# V831.net
KiCad netlist of a schematic drawn in Altium Designer
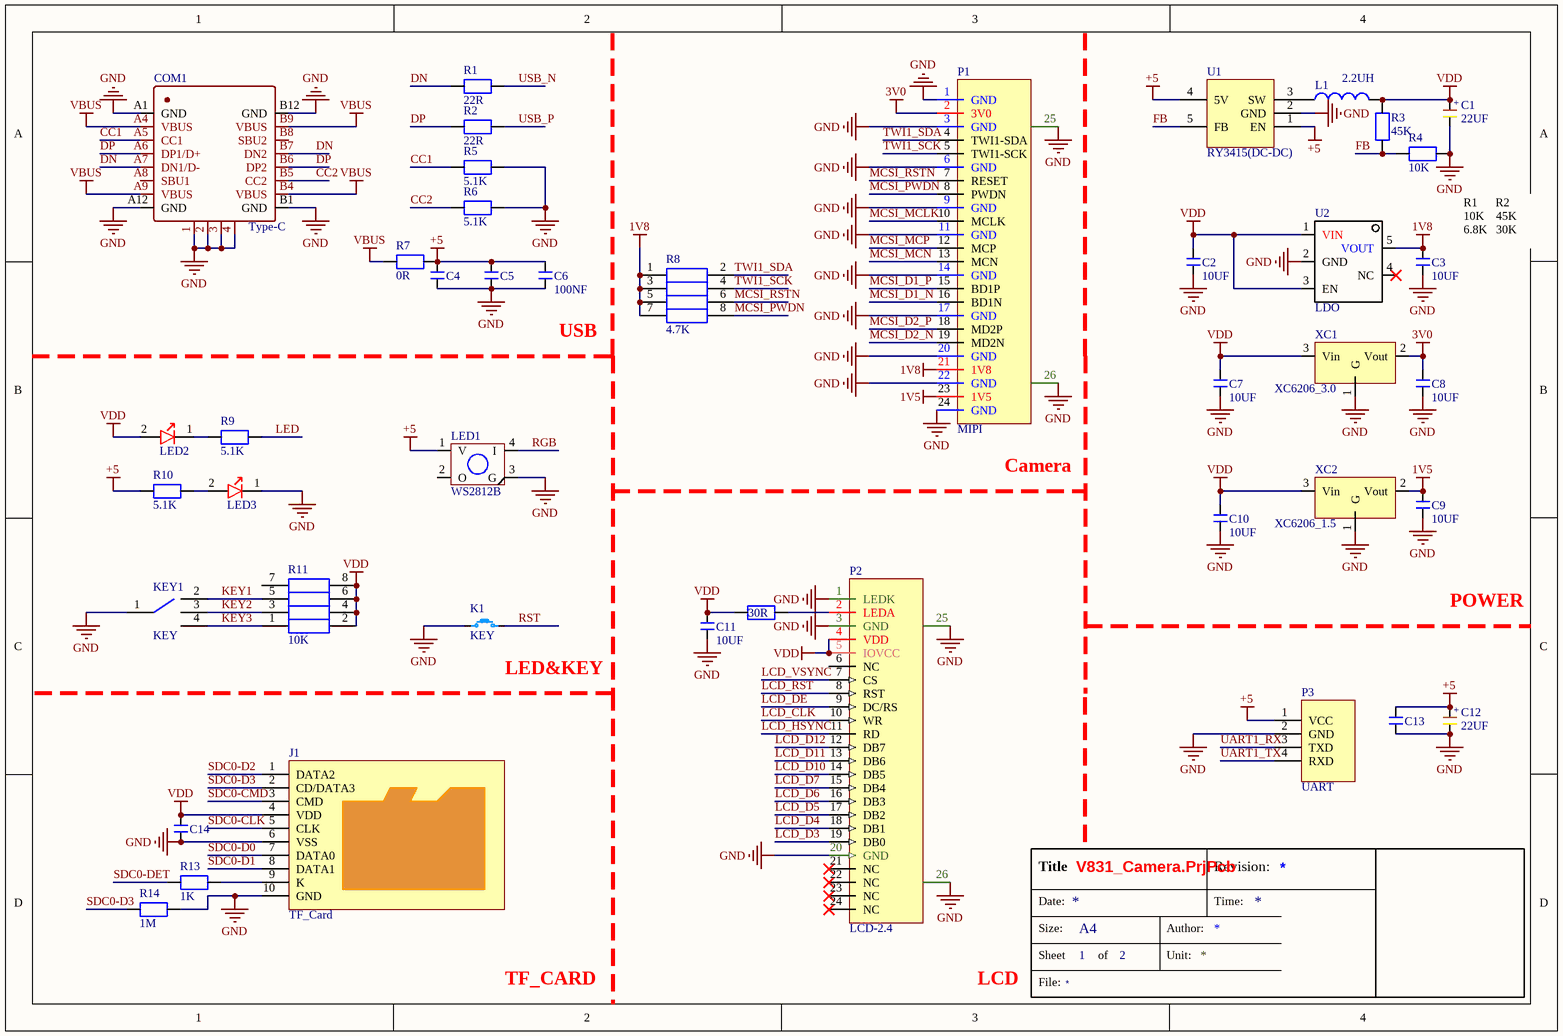
[diagram p0: V831.SchDoc]

(export (version "E")
  (design (tool "Eeschema 10.0.6"))
  (components
    (comp (ref "C1")
      (value "22UF")
      (footprint "CAP_3216_A")
      (description "CAP  6~12V  钽电容")
      (libsource (lib "User") (part "CAP_TA"))
    )
    (comp (ref "C2")
      (value "10UF")
      (footprint "CAP_1206")
      (description "CAP  12~50V")
      (libsource (lib "User") (part "CAP"))
    )
    (comp (ref "C3")
      (value "10UF")
      (footprint "CAP_0603")
      (description "CAP  12~50V")
      (libsource (lib "User") (part "CAP"))
    )
    (comp (ref "C4")
      (value "100NF")
      (footprint "CAP_0603")
      (description "CAP  12~50V")
      (libsource (lib "User") (part "CAP"))
    )
    (comp (ref "C5")
      (value "100NF")
      (footprint "CAP_0603")
      (description "CAP  12~50V")
      (libsource (lib "User") (part "CAP"))
    )
    (comp (ref "C6")
      (value "100NF")
      (footprint "CAP_0603")
      (description "CAP  12~50V")
      (libsource (lib "User") (part "CAP"))
    )
    (comp (ref "C7")
      (value "10UF")
      (footprint "CAP_0603")
      (description "CAP  12~50V")
      (libsource (lib "User") (part "CAP"))
    )
    (comp (ref "C8")
      (value "10UF")
      (footprint "CAP_0603")
      (description "CAP  12~50V")
      (libsource (lib "User") (part "CAP"))
    )
    (comp (ref "C9")
      (value "10UF")
      (footprint "CAP_0603")
      (description "CAP  12~50V")
      (libsource (lib "User") (part "CAP"))
    )
    (comp (ref "C10")
      (value "10UF")
      (footprint "CAP_0603")
      (description "CAP  12~50V")
      (libsource (lib "User") (part "CAP"))
    )
    (comp (ref "C11")
      (value "10UF")
      (footprint "CAP_0603")
      (description "CAP  12~50V")
      (libsource (lib "User") (part "CAP"))
    )
    (comp (ref "C12")
      (value "22UF")
      (footprint "CAP_3216_A")
      (description "CAP  6~12V  钽电容")
      (libsource (lib "User") (part "CAP_TA"))
    )
    (comp (ref "C13")
      (value "100NF")
      (footprint "CAP_0603")
      (description "CAP  12~50V")
      (libsource (lib "User") (part "CAP"))
    )
    (comp (ref "C14")
      (value "100NF")
      (footprint "CAP_0603")
      (description "CAP  12~50V")
      (libsource (lib "User") (part "CAP"))
    )
    (comp (ref "COM1")
      (value "Type-C")
      (footprint "USB-Type-C_16A")
      (description "USB")
      (libsource (lib "User") (part "USB-type_c"))
    )
    (comp (ref "J1")
      (value "TF_Card")
      (footprint "TF_Card")
      (description "TF卡座")
      (libsource (lib "User") (part "TF_Card"))
    )
    (comp (ref "K1")
      (value "KEY")
      (footprint "KEY_SMD-4P")
      (description "Key")
      (libsource (lib "User") (part "KEY"))
    )
    (comp (ref "KEY1")
      (value "KEY")
      (footprint "KEY-K1-1502SA-LY-K3")
      (libsource (lib "User") (part "LY-K3"))
    )
    (comp (ref "L1")
      (value "2.2UH")
      (footprint "INDUCTANCE_4*4")
      (description "Inductor")
      (fields (field (name "PUBLISHER") "Altium Limited"))
      (libsource (lib "User") (part "Inductor"))
    )
    (comp (ref "LED1")
      (value "WS2812B")
      (footprint "WS2812B")
      (description "LED")
      (libsource (lib "User") (part "WS2812B"))
    )
    (comp (ref "LED2")
      (value "LED_R/G/B/Y")
      (footprint "LED_0603_B")
      (description "LED")
      (libsource (lib "User") (part "LED_SMT"))
    )
    (comp (ref "LED3")
      (value "LED_R/G/B/Y")
      (footprint "LED_0603_R")
      (description "LED")
      (libsource (lib "User") (part "LED_SMT"))
    )
    (comp (ref "P1")
      (value "MIPI")
      (footprint "FPC-24Pin")
      (description "OV2465&VS3205")
      (libsource (lib "User") (part "MIPI"))
    )
    (comp (ref "P2")
      (value "LCD-2.4")
      (footprint "FPC-24PIN-FB")
      (description "Show 2.4-2.8寸")
      (libsource (lib "User") (part "LCD-ST7789-Pin24"))
    )
    (comp (ref "P3")
      (value "UART")
      (footprint "XH2.54-WS-4P")
      (description "Header")
      (libsource (lib "User") (part "UART"))
    )
    (comp (ref "R1")
      (value "22R")
      (footprint "RESC_0603_2")
      (description "RES 贴片")
      (libsource (lib "User") (part "RES"))
    )
    (comp (ref "R2")
      (value "22R")
      (footprint "RESC_0603_2")
      (description "RES 贴片")
      (libsource (lib "User") (part "RES"))
    )
    (comp (ref "R3")
      (value "45K")
      (footprint "RESC_0603_2")
      (description "RES 贴片")
      (libsource (lib "User") (part "RES"))
    )
    (comp (ref "R4")
      (value "10K")
      (footprint "RESC_0603_2")
      (description "RES 贴片")
      (libsource (lib "User") (part "RES"))
    )
    (comp (ref "R5")
      (value "5.1K")
      (footprint "RESC_0603_2")
      (description "RES 贴片")
      (libsource (lib "User") (part "RES"))
    )
    (comp (ref "R6")
      (value "5.1K")
      (footprint "RESC_0603_2")
      (description "RES 贴片")
      (libsource (lib "User") (part "RES"))
    )
    (comp (ref "R7")
      (value "0R")
      (footprint "RESC_0603_2")
      (description "RES 贴片")
      (libsource (lib "User") (part "RES"))
    )
    (comp (ref "R8")
      (value "4.7K")
      (footprint "RESC_0603_4")
      (description "RES")
      (libsource (lib "User") (part "RES_P4"))
    )
    (comp (ref "R9")
      (value "5.1K")
      (footprint "RESC_0603_2")
      (description "RES 贴片")
      (libsource (lib "User") (part "RES"))
    )
    (comp (ref "R10")
      (value "5.1K")
      (footprint "RESC_0603_2")
      (description "RES 贴片")
      (libsource (lib "User") (part "RES"))
    )
    (comp (ref "R11")
      (value "10K")
      (footprint "RESC_0603_4")
      (description "RES")
      (libsource (lib "User") (part "RES_P4"))
    )
    (comp (ref "R12")
      (value "30R")
      (footprint "RESC_0603_2")
      (description "RES 贴片")
      (libsource (lib "User") (part "RES"))
    )
    (comp (ref "R13")
      (value "1K")
      (footprint "RESC_0603_2")
      (description "RES 贴片")
      (libsource (lib "User") (part "RES"))
    )
    (comp (ref "R14")
      (value "1M")
      (footprint "RESC_0603_2")
      (description "RES 贴片")
      (libsource (lib "User") (part "RES"))
    )
    (comp (ref "U1") (value "RY3415(DC-DC)") (footprint "SOT23_5") (libsource (lib "User") (part "RY3415")))
    (comp (ref "U2")
      (value "LDO")
      (footprint "SOT23_5")
      (description "LDO  3.3V  500ma")
      (libsource (lib "User") (part "LDO_SOT23-5"))
    )
    (comp (ref "XC1")
      (value "XC6206_3.0")
      (footprint "SOT23_3")
      (description "DC-DC")
      (libsource (lib "User") (part "XC6206"))
    )
    (comp (ref "XC2")
      (value "XC6206_1.5")
      (footprint "SOT23_3")
      (description "DC-DC")
      (libsource (lib "User") (part "XC6206"))
    )
  )
  (nets
    (net (code "1") (name "+5") (class "Default")
      (node (ref "C12") (pin "1") (pinfunction "0_1") (pintype "passive"))
      (node (ref "C13") (pin "2") (pinfunction "0_2") (pintype "passive"))
      (node (ref "C4") (pin "2") (pinfunction "0_2") (pintype "passive"))
      (node (ref "C5") (pin "2") (pinfunction "0_2") (pintype "passive"))
      (node (ref "C6") (pin "2") (pinfunction "0_2") (pintype "passive"))
      (node (ref "LED1") (pin "1") (pinfunction "V_1") (pintype "passive"))
      (node (ref "P3") (pin "1") (pinfunction "VCC_1") (pintype "passive"))
      (node (ref "R10") (pin "1") (pinfunction "1_1") (pintype "passive"))
      (node (ref "R7") (pin "2") (pinfunction "2_2") (pintype "passive"))
      (node (ref "U1") (pin "1") (pinfunction "EN_1") (pintype "passive"))
      (node (ref "U1") (pin "4") (pinfunction "5V_4") (pintype "passive"))
    )
    (net (code "2") (name "/CC1") (class "Default")
      (node (ref "COM1") (pin "A5") (pinfunction "CC1_A5") (pintype "passive"))
      (node (ref "R5") (pin "1") (pinfunction "1_1") (pintype "passive"))
    )
    (net (code "3") (name "/CC2") (class "Default")
      (node (ref "COM1") (pin "B5") (pinfunction "CC2_B5") (pintype "passive"))
      (node (ref "R6") (pin "1") (pinfunction "1_1") (pintype "passive"))
    )
    (net (code "4") (name "/DN") (class "Default")
      (node (ref "COM1") (pin "A7") (pinfunction "DN1/D-_A7") (pintype "passive"))
      (node (ref "COM1") (pin "B7") (pinfunction "DN2_B7") (pintype "passive"))
      (node (ref "R1") (pin "1") (pinfunction "1_1") (pintype "passive"))
    )
    (net (code "5") (name "/DP") (class "Default")
      (node (ref "COM1") (pin "A6") (pinfunction "DP1/D+_A6") (pintype "passive"))
      (node (ref "COM1") (pin "B6") (pinfunction "DP2_B6") (pintype "passive"))
      (node (ref "R2") (pin "1") (pinfunction "1_1") (pintype "passive"))
    )
    (net (code "6") (name "/FB") (class "Default")
      (node (ref "R3") (pin "2") (pinfunction "2_2") (pintype "passive"))
      (node (ref "R4") (pin "1") (pinfunction "1_1") (pintype "passive"))
      (node (ref "U1") (pin "5") (pinfunction "FB_5") (pintype "passive"))
    )
    (net (code "7") (name "/KEY1") (class "Default")
      (node (ref "KEY1") (pin "2") (pinfunction "2_2") (pintype "passive"))
      (node (ref "R11") (pin "5") (pinfunction "5_5") (pintype "passive"))
    )
    (net (code "8") (name "/KEY2") (class "Default")
      (node (ref "KEY1") (pin "3") (pinfunction "3_3") (pintype "passive"))
      (node (ref "R11") (pin "3") (pinfunction "3_3") (pintype "passive"))
    )
    (net (code "9") (name "/KEY3") (class "Default")
      (node (ref "KEY1") (pin "4") (pinfunction "4_4") (pintype "passive"))
      (node (ref "R11") (pin "1") (pinfunction "1_1") (pintype "passive"))
    )
    (net (code "10") (name "/LCD_CLK") (class "Default")
      (node (ref "P2") (pin "10") (pinfunction "WR_10") (pintype "input"))
    )
    (net (code "11") (name "/LCD_D3") (class "Default")
      (node (ref "P2") (pin "19") (pinfunction "DB0_19") (pintype "input"))
    )
    (net (code "12") (name "/LCD_D4") (class "Default")
      (node (ref "P2") (pin "18") (pinfunction "DB1_18") (pintype "input"))
    )
    (net (code "13") (name "/LCD_D5") (class "Default")
      (node (ref "P2") (pin "17") (pinfunction "DB2_17") (pintype "input"))
    )
    (net (code "14") (name "/LCD_D6") (class "Default")
      (node (ref "P2") (pin "16") (pinfunction "DB3_16") (pintype "input"))
    )
    (net (code "15") (name "/LCD_D7") (class "Default")
      (node (ref "P2") (pin "15") (pinfunction "DB4_15") (pintype "input"))
    )
    (net (code "16") (name "/LCD_D10") (class "Default")
      (node (ref "P2") (pin "14") (pinfunction "DB5_14") (pintype "input"))
    )
    (net (code "17") (name "/LCD_D11") (class "Default")
      (node (ref "P2") (pin "13") (pinfunction "DB6_13") (pintype "input"))
    )
    (net (code "18") (name "/LCD_D12") (class "Default")
      (node (ref "P2") (pin "12") (pinfunction "DB7_12") (pintype "input"))
    )
    (net (code "19") (name "/LCD_DE") (class "Default")
      (node (ref "P2") (pin "9") (pinfunction "DC/RS_9") (pintype "input"))
    )
    (net (code "20") (name "/LCD_HSYNC") (class "Default")
      (node (ref "P2") (pin "11") (pinfunction "RD_11") (pintype "passive"))
    )
    (net (code "21") (name "/LCD_RST") (class "Default")
      (node (ref "P2") (pin "8") (pinfunction "RST_8") (pintype "input"))
    )
    (net (code "22") (name "/LCD_VSYNC") (class "Default")
      (node (ref "P2") (pin "7") (pinfunction "CS_7") (pintype "input"))
    )
    (net (code "23") (name "/LED") (class "Default")
      (node (ref "R9") (pin "2") (pinfunction "2_2") (pintype "passive"))
    )
    (net (code "24") (name "/MCSI_D1_N") (class "Default")
      (node (ref "P1") (pin "16") (pinfunction "BD1N_16") (pintype "passive"))
    )
    (net (code "25") (name "/MCSI_D1_P") (class "Default")
      (node (ref "P1") (pin "15") (pinfunction "BD1P_15") (pintype "passive"))
    )
    (net (code "26") (name "/MCSI_D2_N") (class "Default")
      (node (ref "P1") (pin "19") (pinfunction "MD2N_19") (pintype "passive"))
    )
    (net (code "27") (name "/MCSI_D2_P") (class "Default")
      (node (ref "P1") (pin "18") (pinfunction "MD2P_18") (pintype "passive"))
    )
    (net (code "28") (name "/MCSI_MCLK") (class "Default")
      (node (ref "P1") (pin "10") (pinfunction "MCLK_10") (pintype "passive"))
    )
    (net (code "29") (name "/MCSI_MCN") (class "Default")
      (node (ref "P1") (pin "13") (pinfunction "MCN_13") (pintype "passive"))
    )
    (net (code "30") (name "/MCSI_MCP") (class "Default")
      (node (ref "P1") (pin "12") (pinfunction "MCP_12") (pintype "passive"))
    )
    (net (code "31") (name "/MCSI_PWDN") (class "Default")
      (node (ref "P1") (pin "8") (pinfunction "PWDN_8") (pintype "passive"))
      (node (ref "R8") (pin "8") (pinfunction "8_8") (pintype "passive"))
    )
    (net (code "32") (name "/MCSI_RSTN") (class "Default")
      (node (ref "P1") (pin "7") (pinfunction "RESET_7") (pintype "passive"))
      (node (ref "R8") (pin "6") (pinfunction "6_6") (pintype "passive"))
    )
    (net (code "33") (name "/RGB") (class "Default")
      (node (ref "LED1") (pin "4") (pinfunction "I_4") (pintype "passive"))
    )
    (net (code "34") (name "/RST") (class "Default") (node (ref "K1") (pin "2") (pintype "passive")))
    (net (code "35") (name "/SDC0-CLK") (class "Default")
      (node (ref "J1") (pin "5") (pinfunction "CLK_5") (pintype "passive"))
    )
    (net (code "36") (name "/SDC0-CMD") (class "Default")
      (node (ref "J1") (pin "3") (pinfunction "CMD_3") (pintype "passive"))
    )
    (net (code "37") (name "/SDC0-D0") (class "Default")
      (node (ref "J1") (pin "7") (pinfunction "DATA0_7") (pintype "passive"))
    )
    (net (code "38") (name "/SDC0-D1") (class "Default")
      (node (ref "J1") (pin "8") (pinfunction "DATA1_8") (pintype "passive"))
    )
    (net (code "39") (name "/SDC0-D2") (class "Default")
      (node (ref "J1") (pin "1") (pinfunction "DATA2_1") (pintype "passive"))
    )
    (net (code "40") (name "/SDC0-D3") (class "Default")
      (node (ref "J1") (pin "2") (pinfunction "CD/DATA3_2") (pintype "passive"))
      (node (ref "R14") (pin "1") (pinfunction "1_1") (pintype "passive"))
    )
    (net (code "41") (name "/SDC0-DET") (class "Default")
      (node (ref "R13") (pin "1") (pinfunction "1_1") (pintype "passive"))
    )
    (net (code "42") (name "/TWI1_SCK") (class "Default")
      (node (ref "P1") (pin "5") (pinfunction "TWI1-SCK_5") (pintype "passive"))
      (node (ref "R8") (pin "4") (pinfunction "4_4") (pintype "passive"))
    )
    (net (code "43") (name "/TWI1_SDA") (class "Default")
      (node (ref "P1") (pin "4") (pinfunction "TWI1-SDA_4") (pintype "passive"))
      (node (ref "R8") (pin "2") (pinfunction "2_2") (pintype "passive"))
    )
    (net (code "44") (name "/UART1_RX") (class "Default")
      (node (ref "P3") (pin "3") (pinfunction "TXD_3") (pintype "passive"))
    )
    (net (code "45") (name "/UART1_TX") (class "Default")
      (node (ref "P3") (pin "4") (pinfunction "RXD_4") (pintype "passive"))
    )
    (net (code "46") (name "/USB_N") (class "Default")
      (node (ref "R1") (pin "2") (pinfunction "2_2") (pintype "passive"))
    )
    (net (code "47") (name "/USB_P") (class "Default")
      (node (ref "R2") (pin "2") (pinfunction "2_2") (pintype "passive"))
    )
    (net (code "48") (name "1V5") (class "Default")
      (node (ref "C9") (pin "2") (pinfunction "0_2") (pintype "passive"))
      (node (ref "P1") (pin "23") (pinfunction "1V5_23") (pintype "passive"))
      (node (ref "XC2") (pin "2") (pinfunction "Vout_2") (pintype "passive"))
    )
    (net (code "49") (name "1V8") (class "Default")
      (node (ref "C3") (pin "2") (pinfunction "0_2") (pintype "passive"))
      (node (ref "P1") (pin "21") (pinfunction "1V8_21") (pintype "passive"))
      (node (ref "R8") (pin "1") (pinfunction "1_1") (pintype "passive"))
      (node (ref "R8") (pin "3") (pinfunction "3_3") (pintype "passive"))
      (node (ref "R8") (pin "5") (pinfunction "5_5") (pintype "passive"))
      (node (ref "R8") (pin "7") (pinfunction "7_7") (pintype "passive"))
      (node (ref "U2") (pin "5") (pinfunction "VOUT_5") (pintype "passive"))
    )
    (net (code "50") (name "3V0") (class "Default")
      (node (ref "C8") (pin "2") (pinfunction "0_2") (pintype "passive"))
      (node (ref "P1") (pin "2") (pinfunction "3V0_2") (pintype "passive"))
      (node (ref "XC1") (pin "2") (pinfunction "Vout_2") (pintype "passive"))
    )
    (net (code "51") (name "GND") (class "Default")
      (node (ref "C1") (pin "2") (pinfunction "0_2") (pintype "passive"))
      (node (ref "C10") (pin "1") (pinfunction "0_1") (pintype "passive"))
      (node (ref "C11") (pin "1") (pinfunction "0_1") (pintype "passive"))
      (node (ref "C12") (pin "2") (pinfunction "0_2") (pintype "passive"))
      (node (ref "C13") (pin "1") (pinfunction "0_1") (pintype "passive"))
      (node (ref "C14") (pin "1") (pinfunction "0_1") (pintype "passive"))
      (node (ref "C2") (pin "1") (pinfunction "0_1") (pintype "passive"))
      (node (ref "C3") (pin "1") (pinfunction "0_1") (pintype "passive"))
      (node (ref "C4") (pin "1") (pinfunction "0_1") (pintype "passive"))
      (node (ref "C5") (pin "1") (pinfunction "0_1") (pintype "passive"))
      (node (ref "C6") (pin "1") (pinfunction "0_1") (pintype "passive"))
      (node (ref "C7") (pin "1") (pinfunction "0_1") (pintype "passive"))
      (node (ref "C8") (pin "1") (pinfunction "0_1") (pintype "passive"))
      (node (ref "C9") (pin "1") (pinfunction "0_1") (pintype "passive"))
      (node (ref "COM1") (pin "1") (pinfunction "1_1") (pintype "passive"))
      (node (ref "COM1") (pin "2") (pinfunction "2_2") (pintype "passive"))
      (node (ref "COM1") (pin "3") (pinfunction "3_3") (pintype "passive"))
      (node (ref "COM1") (pin "4") (pinfunction "4_4") (pintype "passive"))
      (node (ref "COM1") (pin "A1") (pinfunction "GND_A1") (pintype "passive"))
      (node (ref "COM1") (pin "A12") (pinfunction "GND_A12") (pintype "passive"))
      (node (ref "COM1") (pin "B1") (pinfunction "GND_B1") (pintype "passive"))
      (node (ref "COM1") (pin "B12") (pinfunction "GND_B12") (pintype "passive"))
      (node (ref "J1") (pin "10") (pinfunction "GND_10") (pintype "passive"))
      (node (ref "J1") (pin "6") (pinfunction "VSS_6") (pintype "passive"))
      (node (ref "K1") (pin "1") (pintype "passive"))
      (node (ref "KEY1") (pin "1") (pinfunction "1_1") (pintype "passive"))
      (node (ref "LED1") (pin "3") (pinfunction "G_3") (pintype "passive"))
      (node (ref "LED3") (pin "1") (pinfunction "-_1") (pintype "passive"))
      (node (ref "P1") (pin "1") (pinfunction "GND_1") (pintype "passive"))
      (node (ref "P1") (pin "11") (pinfunction "GND_11") (pintype "passive"))
      (node (ref "P1") (pin "14") (pinfunction "GND_14") (pintype "passive"))
      (node (ref "P1") (pin "17") (pinfunction "GND_17") (pintype "passive"))
      (node (ref "P1") (pin "20") (pinfunction "GND_20") (pintype "passive"))
      (node (ref "P1") (pin "22") (pinfunction "GND_22") (pintype "passive"))
      (node (ref "P1") (pin "24") (pinfunction "GND_24") (pintype "passive"))
      (node (ref "P1") (pin "25") (pinfunction "GND_25") (pintype "passive"))
      (node (ref "P1") (pin "26") (pinfunction "GND_26") (pintype "passive"))
      (node (ref "P1") (pin "3") (pinfunction "GND_3") (pintype "passive"))
      (node (ref "P1") (pin "6") (pinfunction "GND_6") (pintype "passive"))
      (node (ref "P1") (pin "9") (pinfunction "GND_9") (pintype "passive"))
      (node (ref "P2") (pin "1") (pinfunction "LEDK_1") (pintype "passive"))
      (node (ref "P2") (pin "20") (pinfunction "GND_20") (pintype "input"))
      (node (ref "P2") (pin "25") (pinfunction "GND_25") (pintype "passive"))
      (node (ref "P2") (pin "26") (pinfunction "GND_26") (pintype "passive"))
      (node (ref "P2") (pin "3") (pinfunction "GND_3") (pintype "passive"))
      (node (ref "P3") (pin "2") (pinfunction "GND_2") (pintype "passive"))
      (node (ref "R14") (pin "2") (pinfunction "2_2") (pintype "passive"))
      (node (ref "R4") (pin "2") (pinfunction "2_2") (pintype "passive"))
      (node (ref "R5") (pin "2") (pinfunction "2_2") (pintype "passive"))
      (node (ref "R6") (pin "2") (pinfunction "2_2") (pintype "passive"))
      (node (ref "U1") (pin "2") (pinfunction "GND_2") (pintype "passive"))
      (node (ref "U2") (pin "2") (pinfunction "GND_2") (pintype "passive"))
      (node (ref "XC1") (pin "1") (pinfunction "G_1") (pintype "passive"))
      (node (ref "XC2") (pin "1") (pinfunction "G_1") (pintype "passive"))
    )
    (net (code "52") (name "Net-(J1-K)") (class "Default")
      (node (ref "J1") (pin "9") (pinfunction "K_9") (pintype "passive"))
      (node (ref "R13") (pin "2") (pinfunction "2_2") (pintype "passive"))
    )
    (net (code "53") (name "Net-(LED2--)") (class "Default")
      (node (ref "LED2") (pin "1") (pinfunction "-_1") (pintype "passive"))
      (node (ref "R9") (pin "1") (pinfunction "1_1") (pintype "passive"))
    )
    (net (code "54") (name "Net-(LED3-+)") (class "Default")
      (node (ref "LED3") (pin "2") (pinfunction "+_2") (pintype "passive"))
      (node (ref "R10") (pin "2") (pinfunction "2_2") (pintype "passive"))
    )
    (net (code "55") (name "Net-(P2-LEDA)") (class "Default")
      (node (ref "P2") (pin "2") (pinfunction "LEDA_2") (pintype "power_in"))
      (node (ref "R12") (pin "1") (pinfunction "1_1") (pintype "passive"))
    )
    (net (code "56") (name "Net-(U1-SW)") (class "Default")
      (node (ref "L1") (pin "1") (pinfunction "1_1") (pintype "passive"))
      (node (ref "U1") (pin "3") (pinfunction "SW_3") (pintype "passive"))
    )
    (net (code "57") (name "VBUS") (class "Default")
      (node (ref "COM1") (pin "A4") (pinfunction "VBUS_A4") (pintype "passive"))
      (node (ref "COM1") (pin "A9") (pinfunction "VBUS_A9") (pintype "passive"))
      (node (ref "COM1") (pin "B4") (pinfunction "VBUS_B4") (pintype "passive"))
      (node (ref "COM1") (pin "B9") (pinfunction "VBUS_B9") (pintype "passive"))
      (node (ref "R7") (pin "1") (pinfunction "1_1") (pintype "passive"))
    )
    (net (code "58") (name "VDD") (class "Default")
      (node (ref "C1") (pin "1") (pinfunction "0_1") (pintype "passive"))
      (node (ref "C10") (pin "2") (pinfunction "0_2") (pintype "passive"))
      (node (ref "C11") (pin "2") (pinfunction "0_2") (pintype "passive"))
      (node (ref "C14") (pin "2") (pinfunction "0_2") (pintype "passive"))
      (node (ref "C2") (pin "2") (pinfunction "0_2") (pintype "passive"))
      (node (ref "C7") (pin "2") (pinfunction "0_2") (pintype "passive"))
      (node (ref "J1") (pin "4") (pinfunction "VDD_4") (pintype "passive"))
      (node (ref "L1") (pin "2") (pinfunction "2_2") (pintype "passive"))
      (node (ref "LED2") (pin "2") (pinfunction "+_2") (pintype "passive"))
      (node (ref "P2") (pin "4") (pinfunction "VDD_4") (pintype "passive"))
      (node (ref "P2") (pin "5") (pinfunction "IOVCC_5") (pintype "passive"))
      (node (ref "R11") (pin "2") (pinfunction "2_2") (pintype "passive"))
      (node (ref "R11") (pin "4") (pinfunction "4_4") (pintype "passive"))
      (node (ref "R11") (pin "6") (pinfunction "6_6") (pintype "passive"))
      (node (ref "R11") (pin "8") (pinfunction "8_8") (pintype "passive"))
      (node (ref "R12") (pin "2") (pinfunction "2_2") (pintype "passive"))
      (node (ref "R3") (pin "1") (pinfunction "1_1") (pintype "passive"))
      (node (ref "U2") (pin "1") (pinfunction "VIN_1") (pintype "passive"))
      (node (ref "U2") (pin "3") (pinfunction "EN_3") (pintype "passive"))
      (node (ref "XC1") (pin "3") (pinfunction "Vin_3") (pintype "passive"))
      (node (ref "XC2") (pin "3") (pinfunction "Vin_3") (pintype "passive"))
    )
    (net (code "59") (name "unconnected-(COM1-SBU1-PadA8)") (class "Default")
      (node (ref "COM1") (pin "A8") (pinfunction "SBU1_A8") (pintype "passive"))
    )
    (net (code "60") (name "unconnected-(COM1-SBU2-PadB8)") (class "Default")
      (node (ref "COM1") (pin "B8") (pinfunction "SBU2_B8") (pintype "passive"))
    )
    (net (code "61") (name "unconnected-(LED1-O-Pad2)") (class "Default")
      (node (ref "LED1") (pin "2") (pinfunction "O_2") (pintype "passive"))
    )
    (net (code "62") (name "unconnected-(P2-NC-Pad6)") (class "Default")
      (node (ref "P2") (pin "6") (pinfunction "NC_6") (pintype "passive"))
    )
    (net (code "63") (name "unconnected-(P2-NC-Pad21)") (class "Default")
      (node (ref "P2") (pin "21") (pinfunction "NC_21") (pintype "passive+no_connect"))
    )
    (net (code "64") (name "unconnected-(P2-NC-Pad22)") (class "Default")
      (node (ref "P2") (pin "22") (pinfunction "NC_22") (pintype "passive+no_connect"))
    )
    (net (code "65") (name "unconnected-(P2-NC-Pad23)") (class "Default")
      (node (ref "P2") (pin "23") (pinfunction "NC_23") (pintype "passive+no_connect"))
    )
    (net (code "66") (name "unconnected-(P2-NC-Pad24)") (class "Default")
      (node (ref "P2") (pin "24") (pinfunction "NC_24") (pintype "passive+no_connect"))
    )
    (net (code "67") (name "unconnected-(R11-Pad7)") (class "Default")
      (node (ref "R11") (pin "7") (pinfunction "7_7") (pintype "passive"))
    )
    (net (code "68") (name "unconnected-(U2-NC-Pad4)") (class "Default")
      (node (ref "U2") (pin "4") (pinfunction "NC_4") (pintype "passive+no_connect"))
    )
  )
)
